# SparkFun_RTK_Express.net
KiCad netlist of a schematic drawn in EAGLE
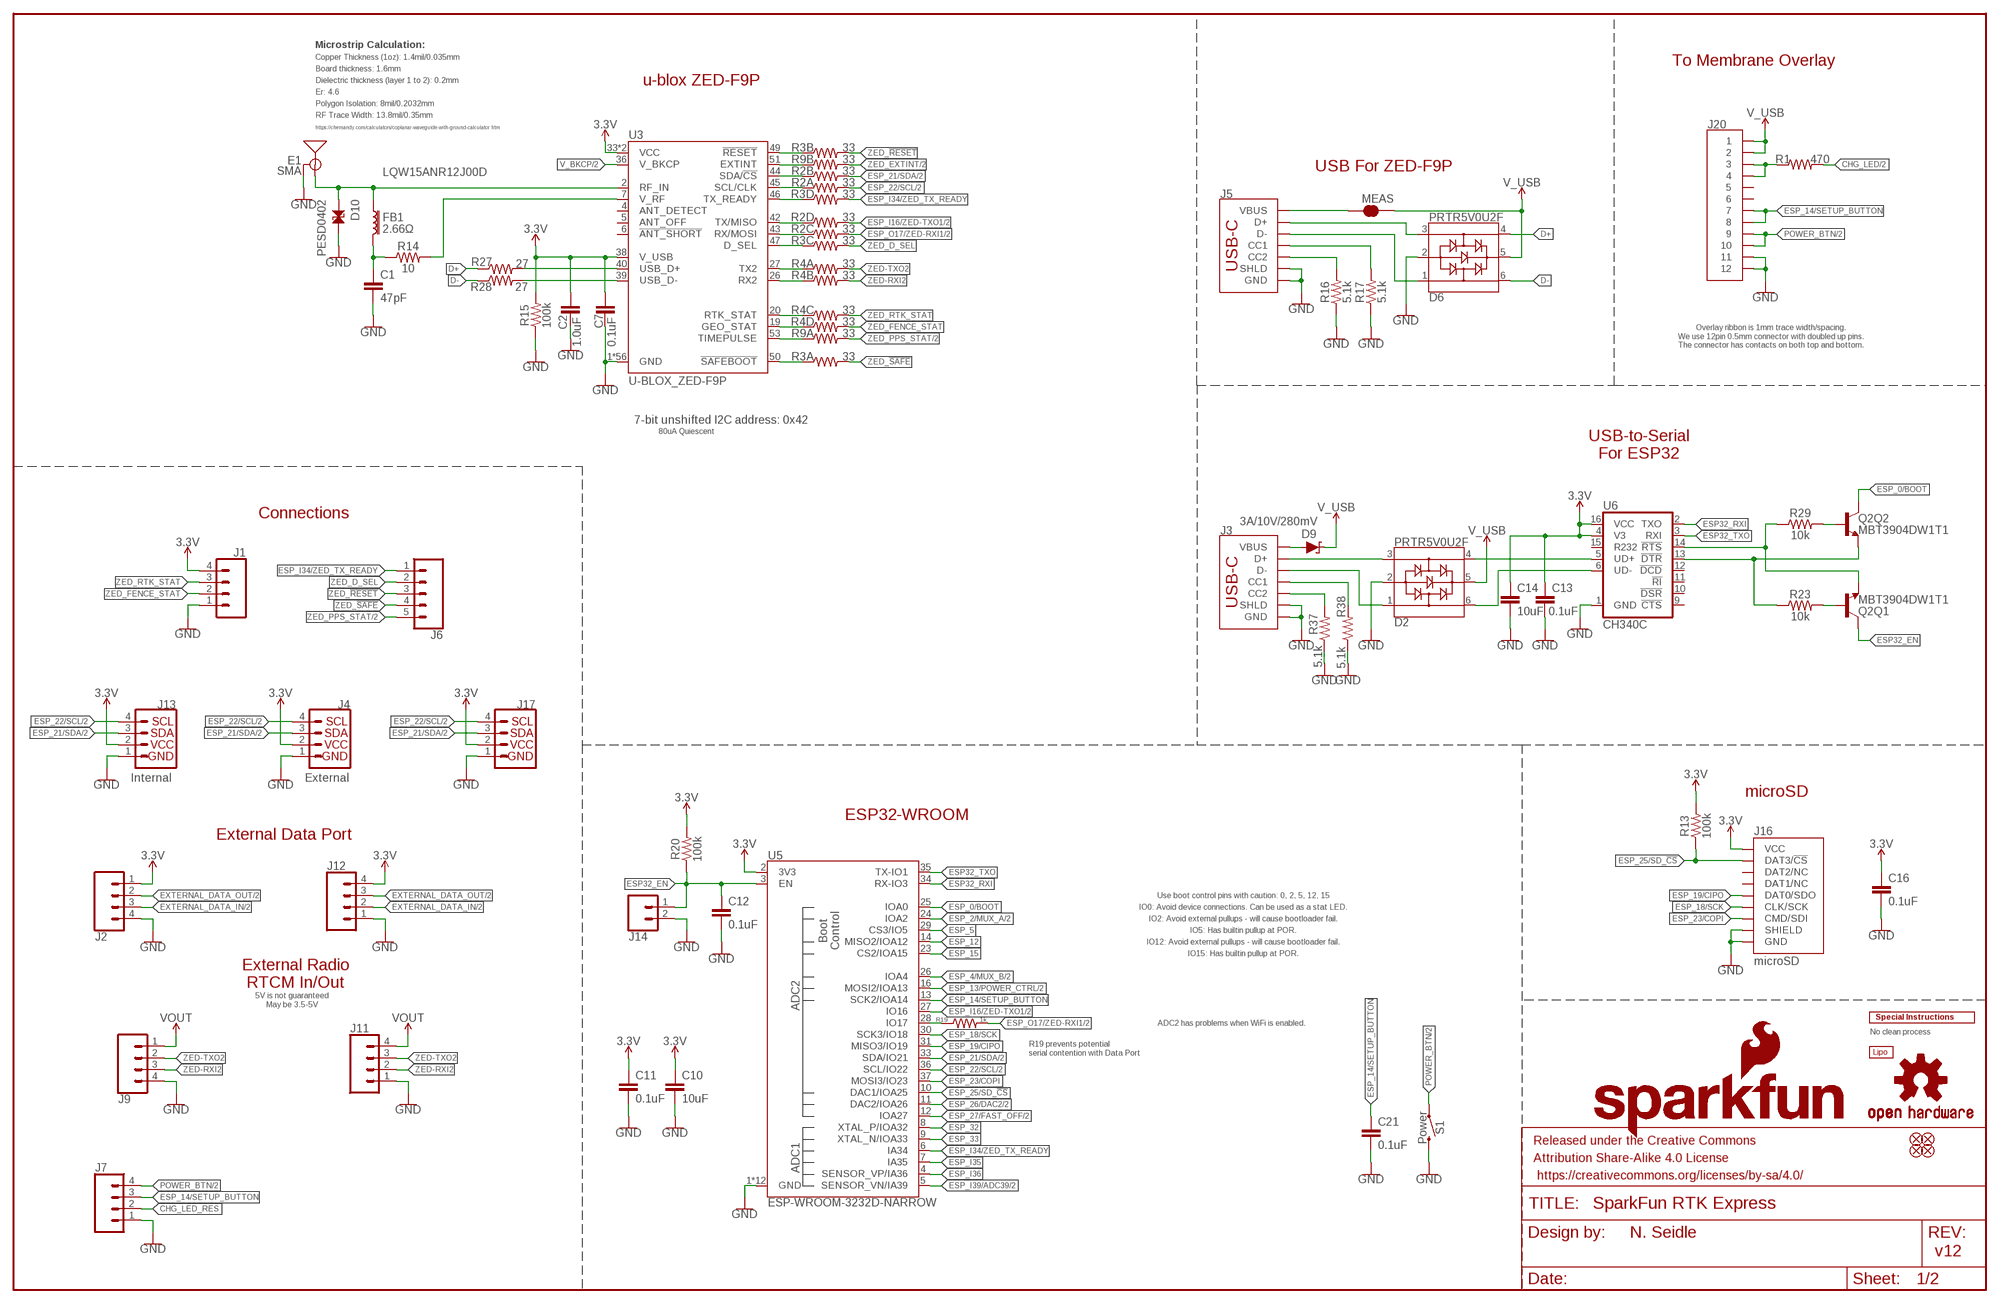
[diagram p0: schematic, sheet 1]
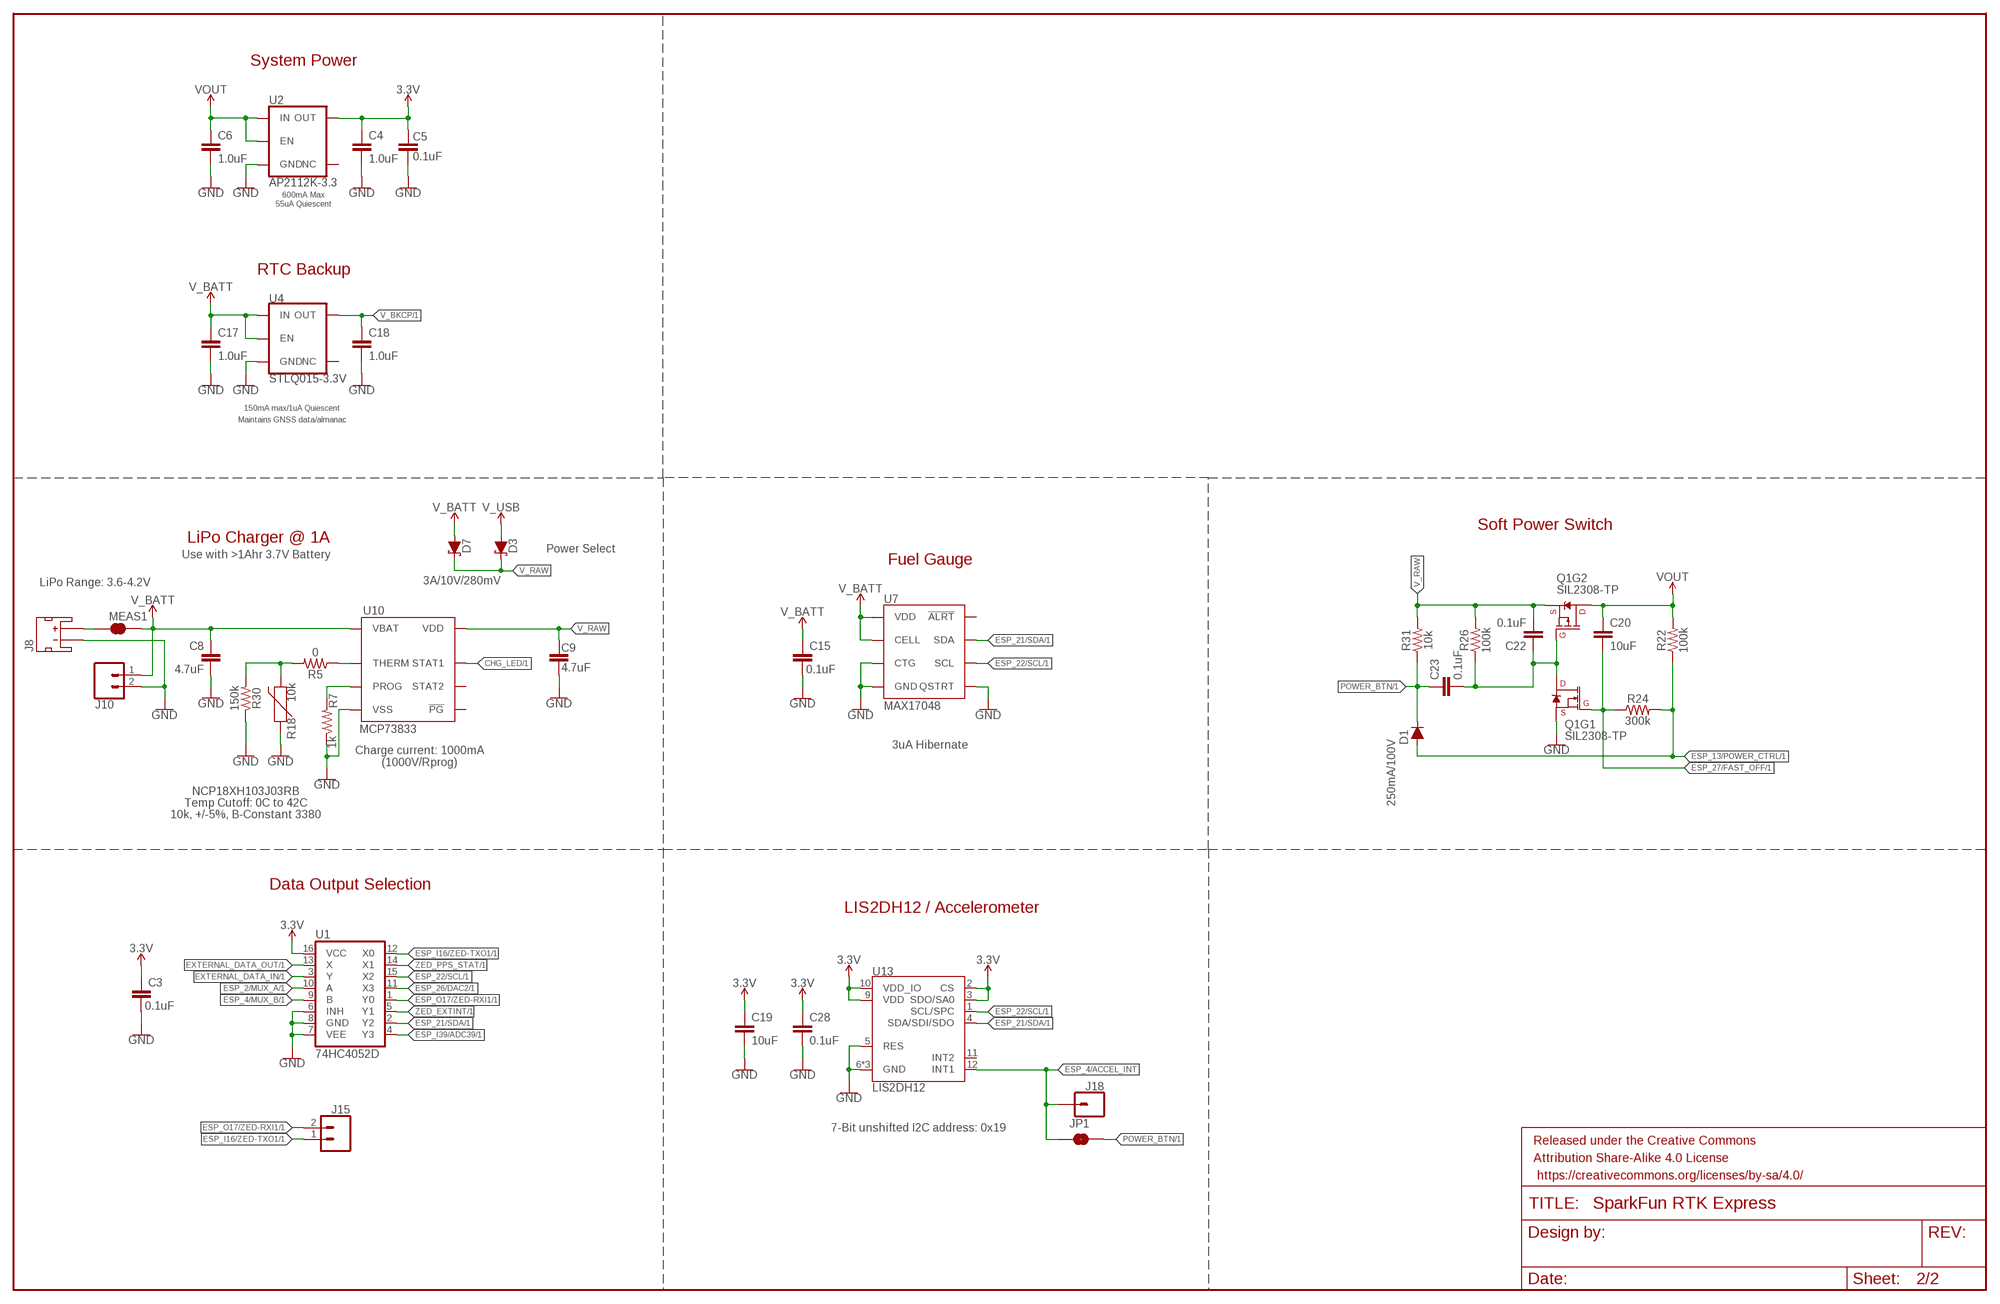
[diagram p1: schematic, sheet 2]

(export (version "E")
  (design (tool "Eeschema 10.0.6"))
  (components
    (comp (ref "C3")
      (value "0.1uF")
      (footprint "eagle-import:0603")
      (libsource (lib "eagle-import") (part "0.1UF-0603-25V-(+80/-20%)"))
    )
    (comp (ref "C4")
      (value "1.0uF")
      (footprint "eagle-import:0603")
      (libsource (lib "eagle-import") (part "1.0UF-0603-16V-10%-X7R"))
    )
    (comp (ref "C5")
      (value "0.1uF")
      (footprint "eagle-import:0603")
      (libsource (lib "eagle-import") (part "0.1UF-0603-25V-5%"))
    )
    (comp (ref "C6")
      (value "1.0uF")
      (footprint "eagle-import:0603")
      (libsource (lib "eagle-import") (part "1.0UF-0603-16V-10%-X7R"))
    )
    (comp (ref "C8")
      (value "4.7uF")
      (footprint "eagle-import:0603")
      (libsource (lib "eagle-import") (part "4.7UF-0603-35V-(20%)"))
    )
    (comp (ref "C9")
      (value "4.7uF")
      (footprint "eagle-import:0603")
      (libsource (lib "eagle-import") (part "4.7UF-0603-35V-(20%)"))
    )
    (comp (ref "C15")
      (value "0.1uF")
      (footprint "eagle-import:0603")
      (libsource (lib "eagle-import") (part "0.1UF-0603-25V-(+80/-20%)"))
    )
    (comp (ref "C17")
      (value "1.0uF")
      (footprint "eagle-import:0603")
      (libsource (lib "eagle-import") (part "1.0UF-0603-16V-10%-X7R"))
    )
    (comp (ref "C18")
      (value "1.0uF")
      (footprint "eagle-import:0603")
      (libsource (lib "eagle-import") (part "1.0UF-0603-16V-10%-X7R"))
    )
    (comp (ref "C19")
      (value "10uF")
      (footprint "eagle-import:0603")
      (libsource (lib "eagle-import") (part "10UF-0603-6.3V-20%"))
    )
    (comp (ref "C20")
      (value "10uF")
      (footprint "eagle-import:0603")
      (libsource (lib "eagle-import") (part "10UF-0603-6.3V-20%"))
    )
    (comp (ref "C22")
      (value "0.1uF")
      (footprint "eagle-import:0603")
      (libsource (lib "eagle-import") (part "0.1UF-0603-25V-5%"))
    )
    (comp (ref "C23")
      (value "0.1uF")
      (footprint "eagle-import:0603")
      (libsource (lib "eagle-import") (part "0.1UF-0603-25V-5%"))
    )
    (comp (ref "C28")
      (value "0.1uF")
      (footprint "eagle-import:0603")
      (libsource (lib "eagle-import") (part "0.1UF-0603-25V-(+80/-20%)"))
    )
    (comp (ref "D1")
      (value "250mA/100V")
      (footprint "eagle-import:SOD-323")
      (libsource (lib "eagle-import") (part "DIODE-BAS16J"))
    )
    (comp (ref "D3")
      (value "3A/10V/280mV")
      (footprint "eagle-import:SOD-323")
      (libsource (lib "eagle-import") (part "DIODE-SCHOTTKY-BAT60A"))
    )
    (comp (ref "D7")
      (value "3A/10V/280mV")
      (footprint "eagle-import:SOD-323")
      (libsource (lib "eagle-import") (part "DIODE-SCHOTTKY-BAT60A"))
    )
    (comp (ref "FRAME3")
      (value "FRAME-LEDGERNO_FOOTPRINT")
      (footprint "eagle-import:DUMMY")
      (libsource (lib "eagle-import") (part "FRAME-LEDGERNO_FOOTPRINT"))
    )
    (comp (ref "J8")
      (value "JST_2MM_MALE")
      (footprint "eagle-import:JST-2-SMD")
      (libsource (lib "eagle-import") (part "JST_2MM_MALE"))
    )
    (comp (ref "J10")
      (value "CONN_021X02_NO_SILK")
      (footprint "eagle-import:1X02_NO_SILK")
      (libsource (lib "eagle-import") (part "CONN_021X02_NO_SILK"))
    )
    (comp (ref "J15")
      (value "CONN_021X02_NO_SILK")
      (footprint "eagle-import:1X02_NO_SILK")
      (libsource (lib "eagle-import") (part "CONN_021X02_NO_SILK"))
    )
    (comp (ref "J18")
      (value "CONN_01PTH_NO_SILK_YES_STOP")
      (footprint "eagle-import:1X01_NO_SILK")
      (libsource (lib "eagle-import") (part "CONN_01PTH_NO_SILK_YES_STOP"))
    )
    (comp (ref "JP1")
      (value "JUMPER-SMT_2_NO_SILK")
      (footprint "eagle-import:SMT-JUMPER_2_NO_SILK")
      (libsource (lib "eagle-import") (part "JUMPER-SMT_2_NO_SILK"))
    )
    (comp (ref "MEAS1")
      (value "JUMPER-COMBO_2_NC_TRACE")
      (footprint "eagle-import:COMBO-JUMPER_2_NC_TRACE")
      (libsource (lib "eagle-import") (part "JUMPER-COMBO_2_NC_TRACE"))
    )
    (comp (ref "Q1")
      (value "SIL2308-TP")
      (footprint "eagle-import:SOT26")
      (libsource (lib "eagle-import") (part "MOSFET_COMPLIMENTARY_PAIR-SIL2308"))
    )
    (comp (ref "R5")
      (value "0")
      (footprint "eagle-import:0603")
      (libsource (lib "eagle-import") (part "0OHM-0603-1/10W"))
    )
    (comp (ref "R7")
      (value "1k")
      (footprint "eagle-import:0603")
      (libsource (lib "eagle-import") (part "1KOHM-0603-1/10W-1%"))
    )
    (comp (ref "R18")
      (value "10k")
      (footprint "eagle-import:0603")
      (libsource (lib "eagle-import") (part "NTC-THERMISTOR-0603"))
    )
    (comp (ref "R22")
      (value "100k")
      (footprint "eagle-import:0603")
      (libsource (lib "eagle-import") (part "100KOHM-0603-1/10W-1%"))
    )
    (comp (ref "R24")
      (value "300k")
      (footprint "eagle-import:0603")
      (libsource (lib "eagle-import") (part "300KOHM-0603-1/10W-1%"))
    )
    (comp (ref "R26")
      (value "100k")
      (footprint "eagle-import:0603")
      (libsource (lib "eagle-import") (part "100KOHM-0603-1/10W-1%"))
    )
    (comp (ref "R30")
      (value "150k")
      (footprint "eagle-import:0603")
      (libsource (lib "eagle-import") (part "150KOHM-0603-1/10W-1%"))
    )
    (comp (ref "R31")
      (value "10k")
      (footprint "eagle-import:0603")
      (libsource (lib "eagle-import") (part "10KOHM-0603-1/10W-1%"))
    )
    (comp (ref "U1")
      (value "74HC4052D")
      (footprint "eagle-import:SO16")
      (libsource (lib "eagle-import") (part "744052DHC"))
    )
    (comp (ref "U2")
      (value "AP2112K-3.3")
      (footprint "eagle-import:SOT23-5")
      (libsource (lib "eagle-import") (part "V_REG_AP2112K-3.3V"))
    )
    (comp (ref "U4")
      (value "STLQ015-3.3V")
      (footprint "eagle-import:SOT23-5")
      (libsource (lib "eagle-import") (part "STLQ015-3.3V"))
    )
    (comp (ref "U7")
      (value "MAX17048")
      (footprint "eagle-import:DFN-8")
      (libsource (lib "eagle-import") (part "MAX17048DFN8"))
    )
    (comp (ref "U10")
      (value "MCP73833")
      (footprint "eagle-import:DFN-10")
      (libsource (lib "eagle-import") (part "MCP73833"))
    )
    (comp (ref "U13")
      (value "LIS2DH12")
      (footprint "eagle-import:LGA-12-LISDH12")
      (libsource (lib "eagle-import") (part "LIS2DH12"))
    )
    (comp (ref "BT1")
      (value "LIPO-OUTLINE1000")
      (footprint "eagle-import:LIPO-1000")
      (libsource (lib "eagle-import") (part "LIPO-OUTLINE1000"))
    )
    (comp (ref "C1")
      (value "47pF")
      (footprint "eagle-import:0402")
      (libsource (lib "eagle-import") (part "47PF-0402-25V-5%-X7R"))
    )
    (comp (ref "C2")
      (value "1.0uF")
      (footprint "eagle-import:0603")
      (libsource (lib "eagle-import") (part "1.0UF-0603-16V-10%-X7R"))
    )
    (comp (ref "C7")
      (value "0.1uF")
      (footprint "eagle-import:0603")
      (libsource (lib "eagle-import") (part "0.1UF-0603-25V-5%"))
    )
    (comp (ref "C10")
      (value "10uF")
      (footprint "eagle-import:0603")
      (libsource (lib "eagle-import") (part "10UF-0603-6.3V-20%"))
    )
    (comp (ref "C11")
      (value "0.1uF")
      (footprint "eagle-import:0603")
      (libsource (lib "eagle-import") (part "0.1UF-0603-25V-(+80/-20%)"))
    )
    (comp (ref "C12")
      (value "0.1uF")
      (footprint "eagle-import:0603")
      (libsource (lib "eagle-import") (part "0.1UF-0603-25V-(+80/-20%)"))
    )
    (comp (ref "C13")
      (value "0.1uF")
      (footprint "eagle-import:0603")
      (libsource (lib "eagle-import") (part "0.1UF-0603-25V-(+80/-20%)"))
    )
    (comp (ref "C14")
      (value "10uF")
      (footprint "eagle-import:0603")
      (libsource (lib "eagle-import") (part "10UF-0603-6.3V-20%"))
    )
    (comp (ref "C16")
      (value "0.1uF")
      (footprint "eagle-import:0603")
      (libsource (lib "eagle-import") (part "0.1UF-0603-25V-(+80/-20%)"))
    )
    (comp (ref "C21")
      (value "0.1uF")
      (footprint "eagle-import:0603")
      (libsource (lib "eagle-import") (part "0.1UF-0603-25V-(+80/-20%)"))
    )
    (comp (ref "D2")
      (value "PRTR5V0U2F")
      (footprint "eagle-import:SOT886")
      (libsource (lib "eagle-import") (part "PRTR5V0U2F"))
    )
    (comp (ref "D6")
      (value "PRTR5V0U2F")
      (footprint "eagle-import:SOT886")
      (libsource (lib "eagle-import") (part "PRTR5V0U2F"))
    )
    (comp (ref "D9")
      (value "3A/10V/280mV")
      (footprint "eagle-import:SOD-323")
      (libsource (lib "eagle-import") (part "DIODE-SCHOTTKY-BAT60A"))
    )
    (comp (ref "D10")
      (value "PESD0402")
      (footprint "eagle-import:0402")
      (fields
        (field (name "DIGIKEY_PART") "PESD0402-140CT-ND")
        (field (name "MOUSE_PART") "650-PESD0402-140")
      )
      (libsource (lib "eagle-import") (part "PESD0402"))
    )
    (comp (ref "E1")
      (value "SMA")
      (footprint "eagle-import:SMA-EDGE")
      (libsource (lib "eagle-import") (part "ANTENNA-SMA-GROUNDEDEDGE_SMA"))
    )
    (comp (ref "FB1")
      (value "2.66Ω")
      (footprint "eagle-import:0402-TIGHT")
      (libsource (lib "eagle-import") (part "FERRITE_BEAD-0402-2.66OHM-1GHZ"))
    )
    (comp (ref "FRAME2")
      (value "FRAME-LEDGER")
      (footprint "eagle-import:CREATIVE_COMMONS")
      (libsource (lib "eagle-import") (part "FRAME-LEDGER"))
    )
    (comp (ref "J1")
      (value "CONN_041X04_NO_SILK_NO_POP")
      (footprint "eagle-import:1X04_NO_SILK")
      (libsource (lib "eagle-import") (part "CONN_041X04_NO_SILK_NO_POP"))
    )
    (comp (ref "J2")
      (value "CONN_04JST-SMD-LOCKING")
      (footprint "eagle-import:JST-4-SMD-1.25MM-LOCKING")
      (libsource (lib "eagle-import") (part "CONN_04JST-SMD-LOCKING"))
    )
    (comp (ref "J3")
      (value "USB Female Type C Connector")
      (footprint "eagle-import:USB-C-16P_4LAYER-PADS")
      (libsource (lib "eagle-import") (part "USB_C_4-LAYER_PADS"))
    )
    (comp (ref "J4")
      (value "External")
      (footprint "eagle-import:JST04_1MM_RA")
      (libsource (lib "eagle-import") (part "I2C_STANDARDQWIIC"))
    )
    (comp (ref "J5")
      (value "USB Female Type C Connector")
      (footprint "eagle-import:USB-C-16P_4LAYER-PADS")
      (libsource (lib "eagle-import") (part "USB_C_4-LAYER_PADS"))
    )
    (comp (ref "J6")
      (value "CONN_05NO_SILK")
      (footprint "eagle-import:1X05_NO_SILK")
      (libsource (lib "eagle-import") (part "CONN_05NO_SILK"))
    )
    (comp (ref "J7")
      (value "CONN_041X04_NO_SILK_NO_POP")
      (footprint "eagle-import:1X04_NO_SILK")
      (libsource (lib "eagle-import") (part "CONN_041X04_NO_SILK_NO_POP"))
    )
    (comp (ref "J9")
      (value "CONN_04JST-SMD-LOCKING")
      (footprint "eagle-import:JST-4-SMD-1.25MM-LOCKING")
      (libsource (lib "eagle-import") (part "CONN_04JST-SMD-LOCKING"))
    )
    (comp (ref "J11")
      (value "CONN_041X04_NO_SILK_NO_POP")
      (footprint "eagle-import:1X04_NO_SILK")
      (libsource (lib "eagle-import") (part "CONN_041X04_NO_SILK_NO_POP"))
    )
    (comp (ref "J12")
      (value "CONN_041X04_NO_SILK_NO_POP")
      (footprint "eagle-import:1X04_NO_SILK")
      (libsource (lib "eagle-import") (part "CONN_041X04_NO_SILK_NO_POP"))
    )
    (comp (ref "J13")
      (value "Internal")
      (footprint "eagle-import:JST04_1MM_RA")
      (libsource (lib "eagle-import") (part "I2C_STANDARDQWIIC"))
    )
    (comp (ref "J14")
      (value "CONN_021X02_NO_SILK")
      (footprint "eagle-import:1X02_NO_SILK")
      (libsource (lib "eagle-import") (part "CONN_021X02_NO_SILK"))
    )
    (comp (ref "J16")
      (value "microSD")
      (footprint "eagle-import:MICRO-SD-SOCKET")
      (libsource (lib "eagle-import") (part "MICRO-SD-SDIOPUSH-PUSH"))
    )
    (comp (ref "J17")
      (value "Qwiic Right Angle")
      (footprint "eagle-import:1X04_NO_SILK")
      (libsource (lib "eagle-import") (part "I2C_STANDARD_NO_SILK"))
    )
    (comp (ref "J20")
      (value "FPC_12_0.5MM_BACKFLIP")
      (footprint "eagle-import:FPC_12_DOUBLESIDED_BACKFLIP")
      (libsource (lib "eagle-import") (part "FPC_12_0.5MM_BACKFLIP"))
    )
    (comp (ref "JP21")
      (value "FIDUCIALUFIDUCIAL")
      (footprint "eagle-import:FIDUCIAL-MICRO")
      (libsource (lib "eagle-import") (part "FIDUCIALUFIDUCIAL"))
    )
    (comp (ref "JP61")
      (value "FIDUCIALUFIDUCIAL")
      (footprint "eagle-import:FIDUCIAL-MICRO")
      (libsource (lib "eagle-import") (part "FIDUCIALUFIDUCIAL"))
    )
    (comp (ref "JP71")
      (value "FIDUCIALUFIDUCIAL")
      (footprint "eagle-import:FIDUCIAL-MICRO")
      (libsource (lib "eagle-import") (part "FIDUCIALUFIDUCIAL"))
    )
    (comp (ref "JP81")
      (value "FIDUCIALUFIDUCIAL")
      (footprint "eagle-import:FIDUCIAL-MICRO")
      (libsource (lib "eagle-import") (part "FIDUCIALUFIDUCIAL"))
    )
    (comp (ref "LOGO1")
      (value "OSHW-LOGOMINI")
      (footprint "eagle-import:OSHW-LOGO-MINI")
      (libsource (lib "eagle-import") (part "OSHW-LOGOMINI"))
    )
    (comp (ref "LOGO2")
      (value "SFE_LOGO_NAME_FLAME.1_INCH")
      (footprint "eagle-import:SFE_LOGO_NAME_FLAME_.1")
      (libsource (lib "eagle-import") (part "SFE_LOGO_NAME_FLAME.1_INCH"))
    )
    (comp (ref "MEAS")
      (value "JUMPER-COMBO_2_NC_TRACE")
      (footprint "eagle-import:COMBO-JUMPER_2_NC_TRACE")
      (libsource (lib "eagle-import") (part "JUMPER-COMBO_2_NC_TRACE"))
    )
    (comp (ref "Q2")
      (value "MBT3904DW1T1")
      (footprint "eagle-import:SC70-6")
      (libsource (lib "eagle-import") (part "TRANS_NPN_DUAL-MBT3904DW1T1"))
    )
    (comp (ref "R1")
      (value "470")
      (footprint "eagle-import:0603")
      (libsource (lib "eagle-import") (part "470OHM-0603-1/10W-1%"))
    )
    (comp (ref "R2")
      (value "33")
      (footprint "eagle-import:1206_RA")
      (libsource (lib "eagle-import") (part "33OHM_RA-1206-1/16W-5%"))
    )
    (comp (ref "R3")
      (value "33")
      (footprint "eagle-import:1206_RA")
      (libsource (lib "eagle-import") (part "33OHM_RA-1206-1/16W-5%"))
    )
    (comp (ref "R4")
      (value "33")
      (footprint "eagle-import:1206_RA")
      (libsource (lib "eagle-import") (part "33OHM_RA-1206-1/16W-5%"))
    )
    (comp (ref "R9")
      (value "33")
      (footprint "eagle-import:1206_RA")
      (libsource (lib "eagle-import") (part "33OHM_RA-1206-1/16W-5%"))
    )
    (comp (ref "R13")
      (value "100k")
      (footprint "eagle-import:0603")
      (libsource (lib "eagle-import") (part "100KOHM-0603-1/10W-1%"))
    )
    (comp (ref "R14")
      (value "10")
      (footprint "eagle-import:0603")
      (libsource (lib "eagle-import") (part "10OHM-0603-1/10W-1%"))
    )
    (comp (ref "R15")
      (value "100k")
      (footprint "eagle-import:0603")
      (libsource (lib "eagle-import") (part "100KOHM-0603-1/10W-1%"))
    )
    (comp (ref "R16")
      (value "5.1k")
      (footprint "eagle-import:0603")
      (libsource (lib "eagle-import") (part "5.1KOHM5.1KOHM-0603-1/10W-1%"))
    )
    (comp (ref "R17")
      (value "5.1k")
      (footprint "eagle-import:0603")
      (libsource (lib "eagle-import") (part "5.1KOHM5.1KOHM-0603-1/10W-1%"))
    )
    (comp (ref "R19")
      (value "1k")
      (footprint "eagle-import:0603")
      (libsource (lib "eagle-import") (part "1KOHM-0603-1/10W-1%"))
    )
    (comp (ref "R20")
      (value "100k")
      (footprint "eagle-import:0603")
      (libsource (lib "eagle-import") (part "100KOHM-0603-1/10W-1%"))
    )
    (comp (ref "R23")
      (value "10k")
      (footprint "eagle-import:0603")
      (libsource (lib "eagle-import") (part "10KOHM-0603-1/10W-1%"))
    )
    (comp (ref "R27")
      (value "27")
      (footprint "eagle-import:0603")
      (libsource (lib "eagle-import") (part "27OHM-0603-1/10W-1%"))
    )
    (comp (ref "R28")
      (value "27")
      (footprint "eagle-import:0603")
      (libsource (lib "eagle-import") (part "27OHM-0603-1/10W-1%"))
    )
    (comp (ref "R29")
      (value "10k")
      (footprint "eagle-import:0603")
      (libsource (lib "eagle-import") (part "10KOHM-0603-1/10W-1%"))
    )
    (comp (ref "R37")
      (value "5.1k")
      (footprint "eagle-import:0603")
      (libsource (lib "eagle-import") (part "5.1KOHM5.1KOHM-0603-1/10W-1%"))
    )
    (comp (ref "R38")
      (value "5.1k")
      (footprint "eagle-import:0603")
      (libsource (lib "eagle-import") (part "5.1KOHM5.1KOHM-0603-1/10W-1%"))
    )
    (comp (ref "S1")
      (value "Power")
      (footprint "eagle-import:TACTILE_SWITCH_SMD_5.2MM")
      (libsource (lib "eagle-import") (part "MOMENTARY-SWITCH-SPST-SMD-5.2MM-TALL"))
    )
    (comp (ref "U$2")
      (value "SPECIAL_INSTRUCTIONS-ORDERING")
      (footprint "eagle-import:ORDERING_INSTRUCTIONS")
      (libsource (lib "eagle-import") (part "SPECIAL_INSTRUCTIONS-ORDERING"))
    )
    (comp (ref "U3")
      (value "U-BLOX_ZED-F9P")
      (footprint "eagle-import:ZED-F9P")
      (libsource (lib "eagle-import") (part "U-BLOX_ZED-F9P"))
    )
    (comp (ref "U5")
      (value "ESP-WROOM-3232D-NARROW")
      (footprint "eagle-import:ESP-WROOM-32D-NARROW")
      (libsource (lib "eagle-import") (part "ESP-WROOM-3232D-NARROW"))
    )
    (comp (ref "U6")
      (value "CH340C")
      (footprint "eagle-import:SO016")
      (libsource (lib "eagle-import") (part "CH340C"))
    )
  )
  (nets
    (net (code "1") (name "3.3V") (class "Default")
      (node (ref "C10") (pin "1") (pinfunction "1_1") (pintype "passive"))
      (node (ref "C11") (pin "1") (pinfunction "1_1") (pintype "passive"))
      (node (ref "C13") (pin "1") (pinfunction "1_1") (pintype "passive"))
      (node (ref "C14") (pin "1") (pinfunction "1_1") (pintype "passive"))
      (node (ref "C16") (pin "1") (pinfunction "1_1") (pintype "passive"))
      (node (ref "C19") (pin "1") (pinfunction "1_1") (pintype "passive"))
      (node (ref "C2") (pin "1") (pinfunction "1_1") (pintype "passive"))
      (node (ref "C28") (pin "1") (pinfunction "1_1") (pintype "passive"))
      (node (ref "C3") (pin "1") (pinfunction "1_1") (pintype "passive"))
      (node (ref "C4") (pin "1") (pinfunction "1_1") (pintype "passive"))
      (node (ref "C5") (pin "2") (pinfunction "2_2") (pintype "passive"))
      (node (ref "C7") (pin "2") (pinfunction "2_2") (pintype "passive"))
      (node (ref "J1") (pin "4") (pinfunction "4_4") (pintype "passive"))
      (node (ref "J12") (pin "4") (pinfunction "4_4") (pintype "passive"))
      (node (ref "J13") (pin "2") (pinfunction "2_2") (pintype "power_in"))
      (node (ref "J16") (pin "VCC") (pinfunction "VCC_VCC") (pintype "bidirectional"))
      (node (ref "J17") (pin "2") (pinfunction "2_2") (pintype "power_in"))
      (node (ref "J2") (pin "1") (pinfunction "1_1") (pintype "passive"))
      (node (ref "J4") (pin "2") (pinfunction "2_2") (pintype "power_in"))
      (node (ref "R13") (pin "2") (pinfunction "2_2") (pintype "passive"))
      (node (ref "R15") (pin "2") (pinfunction "2_2") (pintype "passive"))
      (node (ref "R20") (pin "2") (pinfunction "2_2") (pintype "passive"))
      (node (ref "U1") (pin "16") (pinfunction "VCC_16") (pintype "power_in"))
      (node (ref "U13") (pin "10") (pinfunction "VDD_IO_10") (pintype "bidirectional"))
      (node (ref "U13") (pin "2") (pinfunction "CS_2") (pintype "bidirectional"))
      (node (ref "U13") (pin "3") (pinfunction "SDO/SA0_3") (pintype "bidirectional"))
      (node (ref "U13") (pin "9") (pinfunction "VDD_9") (pintype "bidirectional"))
      (node (ref "U2") (pin "5") (pinfunction "OUT_5") (pintype "passive"))
      (node (ref "U3") (pin "33") (pinfunction "VCC_33") (pintype "bidirectional"))
      (node (ref "U3") (pin "34") (pinfunction "VCC_34") (pintype "bidirectional"))
      (node (ref "U3") (pin "38") (pinfunction "V_USB_38") (pintype "bidirectional"))
      (node (ref "U5") (pin "2") (pinfunction "3V3_2") (pintype "bidirectional"))
      (node (ref "U6") (pin "16") (pinfunction "VCC_16") (pintype "bidirectional"))
      (node (ref "U6") (pin "4") (pinfunction "V3_4") (pintype "bidirectional"))
    )
    (net (code "2") (name "CHG_LED") (class "Default")
      (node (ref "R1") (pin "2") (pinfunction "2_2") (pintype "passive"))
      (node (ref "U10") (pin "3") (pinfunction "STAT1_3") (pintype "bidirectional"))
    )
    (net (code "3") (name "CHG_LED_RES") (class "Default")
      (node (ref "J20") (pin "3") (pinfunction "3_3") (pintype "bidirectional"))
      (node (ref "J20") (pin "4") (pinfunction "4_4") (pintype "bidirectional"))
      (node (ref "J7") (pin "2") (pinfunction "2_2") (pintype "passive"))
      (node (ref "R1") (pin "1") (pinfunction "1_1") (pintype "passive"))
    )
    (net (code "4") (name "D+") (class "Default")
      (node (ref "D6") (pin "4") (pinfunction "4_4") (pintype "bidirectional"))
      (node (ref "R27") (pin "1") (pinfunction "1_1") (pintype "passive"))
    )
    (net (code "5") (name "D-") (class "Default")
      (node (ref "D6") (pin "6") (pinfunction "6_6") (pintype "bidirectional"))
      (node (ref "R28") (pin "1") (pinfunction "1_1") (pintype "passive"))
    )
    (net (code "6") (name "ESP32_EN") (class "Default")
      (node (ref "C12") (pin "1") (pinfunction "1_1") (pintype "passive"))
      (node (ref "J14") (pin "1") (pinfunction "1_1") (pintype "passive"))
      (node (ref "Q2") (pin "3") (pinfunction "C_3") (pintype "passive"))
      (node (ref "R20") (pin "1") (pinfunction "1_1") (pintype "passive"))
      (node (ref "U5") (pin "3") (pinfunction "EN_3") (pintype "bidirectional"))
    )
    (net (code "7") (name "ESP32_RXI") (class "Default")
      (node (ref "U5") (pin "34") (pinfunction "RX-IO3_34") (pintype "bidirectional"))
      (node (ref "U6") (pin "2") (pinfunction "TXO_2") (pintype "bidirectional"))
    )
    (net (code "8") (name "ESP32_TXO") (class "Default")
      (node (ref "U5") (pin "35") (pinfunction "TX-IO1_35") (pintype "bidirectional"))
      (node (ref "U6") (pin "3") (pinfunction "RXI_3") (pintype "bidirectional"))
    )
    (net (code "9") (name "ESP_0{slash}BOOT") (class "Default")
      (node (ref "Q2") (pin "6") (pinfunction "C_6") (pintype "passive"))
      (node (ref "U5") (pin "25") (pinfunction "IOA0_25") (pintype "bidirectional"))
    )
    (net (code "10") (name "ESP_2{slash}MUX_A") (class "Default")
      (node (ref "U1") (pin "10") (pinfunction "A_10") (pintype "input"))
      (node (ref "U5") (pin "24") (pinfunction "IOA2_24") (pintype "bidirectional"))
    )
    (net (code "11") (name "ESP_4{slash}ACCEL_INT") (class "Default")
      (node (ref "J18") (pin "1") (pinfunction "1_1") (pintype "passive"))
      (node (ref "JP1") (pin "1") (pinfunction "1_1") (pintype "passive"))
      (node (ref "U13") (pin "12") (pinfunction "INT1_12") (pintype "bidirectional"))
    )
    (net (code "12") (name "ESP_4{slash}MUX_B") (class "Default")
      (node (ref "U1") (pin "9") (pinfunction "B_9") (pintype "input"))
      (node (ref "U5") (pin "26") (pinfunction "IOA4_26") (pintype "bidirectional"))
    )
    (net (code "13") (name "ESP_5") (class "Default")
      (node (ref "U5") (pin "29") (pinfunction "CS3/IO5_29") (pintype "bidirectional"))
    )
    (net (code "14") (name "ESP_12") (class "Default")
      (node (ref "U5") (pin "14") (pinfunction "MISO2/IOA12_14") (pintype "bidirectional"))
    )
    (net (code "15") (name "ESP_13{slash}POWER_CTRL") (class "Default")
      (node (ref "D1") (pin "A") (pinfunction "A_A") (pintype "passive"))
      (node (ref "R22") (pin "1") (pinfunction "1_1") (pintype "passive"))
      (node (ref "R24") (pin "2") (pinfunction "2_2") (pintype "passive"))
      (node (ref "U5") (pin "16") (pinfunction "MOSI2/IOA13_16") (pintype "bidirectional"))
    )
    (net (code "16") (name "ESP_14{slash}SETUP_BUTTON") (class "Default")
      (node (ref "C21") (pin "1") (pinfunction "1_1") (pintype "passive"))
      (node (ref "J20") (pin "7") (pinfunction "7_7") (pintype "bidirectional"))
      (node (ref "J20") (pin "8") (pinfunction "8_8") (pintype "bidirectional"))
      (node (ref "J7") (pin "3") (pinfunction "3_3") (pintype "passive"))
      (node (ref "U5") (pin "13") (pinfunction "SCK2/IOA14_13") (pintype "bidirectional"))
    )
    (net (code "17") (name "ESP_15") (class "Default")
      (node (ref "U5") (pin "23") (pinfunction "CS2/IOA15_23") (pintype "bidirectional"))
    )
    (net (code "18") (name "ESP_18{slash}SCK") (class "Default")
      (node (ref "J16") (pin "SCLK") (pinfunction "CLK/SCK_SCLK") (pintype "bidirectional"))
      (node (ref "U5") (pin "30") (pinfunction "SCK3/IO18_30") (pintype "bidirectional"))
    )
    (net (code "19") (name "ESP_19{slash}CIPO") (class "Default")
      (node (ref "J16") (pin "DO/DAT0") (pinfunction "DAT0/SDO_DO/DAT0") (pintype "bidirectional"))
      (node (ref "U5") (pin "31") (pinfunction "MISO3/IO19_31") (pintype "bidirectional"))
    )
    (net (code "20") (name "ESP_21{slash}SDA") (class "Default")
      (node (ref "J13") (pin "3") (pinfunction "3_3") (pintype "passive"))
      (node (ref "J17") (pin "3") (pinfunction "3_3") (pintype "passive"))
      (node (ref "J4") (pin "3") (pinfunction "3_3") (pintype "passive"))
      (node (ref "R2") (pin "P7") (pinfunction "2_P7") (pintype "passive"))
      (node (ref "U1") (pin "2") (pinfunction "Y2_2") (pintype "bidirectional"))
      (node (ref "U13") (pin "4") (pinfunction "SDA/SDI/SDO_4") (pintype "bidirectional"))
      (node (ref "U5") (pin "33") (pinfunction "SDA/IO21_33") (pintype "bidirectional"))
      (node (ref "U7") (pin "8") (pinfunction "SDA_8") (pintype "input"))
    )
    (net (code "21") (name "ESP_22{slash}SCL") (class "Default")
      (node (ref "J13") (pin "4") (pinfunction "4_4") (pintype "passive"))
      (node (ref "J17") (pin "4") (pinfunction "4_4") (pintype "passive"))
      (node (ref "J4") (pin "4") (pinfunction "4_4") (pintype "passive"))
      (node (ref "R2") (pin "P8") (pinfunction "2_P8") (pintype "passive"))
      (node (ref "U1") (pin "15") (pinfunction "X2_15") (pintype "bidirectional"))
      (node (ref "U13") (pin "1") (pinfunction "SCL/SPC_1") (pintype "bidirectional"))
      (node (ref "U5") (pin "36") (pinfunction "SCL/IO22_36") (pintype "bidirectional"))
      (node (ref "U7") (pin "7") (pinfunction "SCL_7") (pintype "output"))
    )
    (net (code "22") (name "ESP_23{slash}COPI") (class "Default")
      (node (ref "J16") (pin "DI/CMD") (pinfunction "CMD/SDI_DI/CMD") (pintype "bidirectional"))
      (node (ref "U5") (pin "37") (pinfunction "MOSI3/IO23_37") (pintype "bidirectional"))
    )
    (net (code "23") (name "ESP_25{slash}SD_~{CS}") (class "Default")
      (node (ref "J16") (pin "CS/DAT3") (pinfunction "DAT3/~{CS}_CS/DAT3") (pintype "bidirectional"))
      (node (ref "R13") (pin "1") (pinfunction "1_1") (pintype "passive"))
      (node (ref "U5") (pin "10") (pinfunction "DAC1/IOA25_10") (pintype "bidirectional"))
    )
    (net (code "24") (name "ESP_26{slash}DAC2") (class "Default")
      (node (ref "U1") (pin "11") (pinfunction "X3_11") (pintype "bidirectional"))
      (node (ref "U5") (pin "11") (pinfunction "DAC2/IOA26_11") (pintype "bidirectional"))
    )
    (net (code "25") (name "ESP_27{slash}FAST_OFF") (class "Default")
      (node (ref "C20") (pin "2") (pinfunction "2_2") (pintype "passive"))
      (node (ref "Q1") (pin "G1") (pinfunction "G_G1") (pintype "bidirectional"))
      (node (ref "R24") (pin "1") (pinfunction "1_1") (pintype "passive"))
      (node (ref "U5") (pin "12") (pinfunction "IOA27_12") (pintype "bidirectional"))
    )
    (net (code "26") (name "ESP_32") (class "Default")
      (node (ref "U5") (pin "8") (pinfunction "XTAL_P/IOA32_8") (pintype "bidirectional"))
    )
    (net (code "27") (name "ESP_33") (class "Default")
      (node (ref "U5") (pin "9") (pinfunction "XTAL_N/IOA33_9") (pintype "bidirectional"))
    )
    (net (code "28") (name "ESP_I16{slash}ZED-TXO1") (class "Default")
      (node (ref "J15") (pin "1") (pinfunction "1_1") (pintype "passive"))
      (node (ref "R2") (pin "P5") (pinfunction "2_P5") (pintype "passive"))
      (node (ref "U1") (pin "12") (pinfunction "X0_12") (pintype "bidirectional"))
      (node (ref "U5") (pin "27") (pinfunction "IO16_27") (pintype "bidirectional"))
    )
    (net (code "29") (name "ESP_I34{slash}ZED_TX_READY") (class "Default")
      (node (ref "J6") (pin "1") (pinfunction "1_1") (pintype "passive"))
      (node (ref "R3") (pin "P5") (pinfunction "2_P5") (pintype "passive"))
      (node (ref "U5") (pin "6") (pinfunction "IA34_6") (pintype "bidirectional"))
    )
    (net (code "30") (name "ESP_I35") (class "Default")
      (node (ref "U5") (pin "7") (pinfunction "IA35_7") (pintype "bidirectional"))
    )
    (net (code "31") (name "ESP_I36") (class "Default")
      (node (ref "U5") (pin "4") (pinfunction "SENSOR_VP/IA36_4") (pintype "bidirectional"))
    )
    (net (code "32") (name "ESP_I39{slash}ADC39") (class "Default")
      (node (ref "U1") (pin "4") (pinfunction "Y3_4") (pintype "bidirectional"))
      (node (ref "U5") (pin "5") (pinfunction "SENSOR_VN/IA39_5") (pintype "bidirectional"))
    )
    (net (code "33") (name "ESP_O17{slash}ZED-RXI1") (class "Default")
      (node (ref "J15") (pin "2") (pinfunction "2_2") (pintype "passive"))
      (node (ref "R19") (pin "2") (pinfunction "2_2") (pintype "passive"))
      (node (ref "R2") (pin "P6") (pinfunction "2_P6") (pintype "passive"))
      (node (ref "U1") (pin "1") (pinfunction "Y0_1") (pintype "bidirectional"))
    )
    (net (code "34") (name "EXTERNAL_DATA_IN") (class "Default")
      (node (ref "J12") (pin "2") (pinfunction "2_2") (pintype "passive"))
      (node (ref "J2") (pin "3") (pinfunction "3_3") (pintype "passive"))
      (node (ref "U1") (pin "3") (pinfunction "Y_3") (pintype "bidirectional"))
    )
    (net (code "35") (name "EXTERNAL_DATA_OUT") (class "Default")
      (node (ref "J12") (pin "3") (pinfunction "3_3") (pintype "passive"))
      (node (ref "J2") (pin "2") (pinfunction "2_2") (pintype "passive"))
      (node (ref "U1") (pin "13") (pinfunction "X_13") (pintype "bidirectional"))
    )
    (net (code "36") (name "GND") (class "Default")
      (node (ref "C1") (pin "2") (pinfunction "2_2") (pintype "passive"))
      (node (ref "C10") (pin "2") (pinfunction "2_2") (pintype "passive"))
      (node (ref "C11") (pin "2") (pinfunction "2_2") (pintype "passive"))
      (node (ref "C12") (pin "2") (pinfunction "2_2") (pintype "passive"))
      (node (ref "C13") (pin "2") (pinfunction "2_2") (pintype "passive"))
      (node (ref "C14") (pin "2") (pinfunction "2_2") (pintype "passive"))
      (node (ref "C15") (pin "2") (pinfunction "2_2") (pintype "passive"))
      (node (ref "C16") (pin "2") (pinfunction "2_2") (pintype "passive"))
      (node (ref "C17") (pin "2") (pinfunction "2_2") (pintype "passive"))
      (node (ref "C18") (pin "2") (pinfunction "2_2") (pintype "passive"))
      (node (ref "C19") (pin "2") (pinfunction "2_2") (pintype "passive"))
      (node (ref "C2") (pin "2") (pinfunction "2_2") (pintype "passive"))
      (node (ref "C21") (pin "2") (pinfunction "2_2") (pintype "passive"))
      (node (ref "C28") (pin "2") (pinfunction "2_2") (pintype "passive"))
      (node (ref "C3") (pin "2") (pinfunction "2_2") (pintype "passive"))
      (node (ref "C4") (pin "2") (pinfunction "2_2") (pintype "passive"))
      (node (ref "C5") (pin "1") (pinfunction "1_1") (pintype "passive"))
      (node (ref "C6") (pin "2") (pinfunction "2_2") (pintype "passive"))
      (node (ref "C7") (pin "1") (pinfunction "1_1") (pintype "passive"))
      (node (ref "C8") (pin "2") (pinfunction "2_2") (pintype "passive"))
      (node (ref "C9") (pin "2") (pinfunction "2_2") (pintype "passive"))
      (node (ref "D10") (pin "2") (pinfunction "2_2") (pintype "bidirectional"))
      (node (ref "D2") (pin "2") (pinfunction "2_2") (pintype "power_in"))
      (node (ref "D6") (pin "2") (pinfunction "2_2") (pintype "power_in"))
      (node (ref "E1") (pin "GND@0") (pinfunction "GND_GND@0") (pintype "bidirectional"))
      (node (ref "E1") (pin "GND@1") (pinfunction "GND_GND@1") (pintype "bidirectional"))
      (node (ref "E1") (pin "GND@2") (pinfunction "GND_GND@2") (pintype "bidirectional"))
      (node (ref "E1") (pin "GND@3") (pinfunction "GND_GND@3") (pintype "bidirectional"))
      (node (ref "J1") (pin "1") (pinfunction "1_1") (pintype "passive"))
      (node (ref "J10") (pin "2") (pinfunction "2_2") (pintype "passive"))
      (node (ref "J11") (pin "1") (pinfunction "1_1") (pintype "passive"))
      (node (ref "J12") (pin "1") (pinfunction "1_1") (pintype "passive"))
      (node (ref "J13") (pin "1") (pinfunction "1_1") (pintype "power_in"))
      (node (ref "J14") (pin "2") (pinfunction "2_2") (pintype "passive"))
      (node (ref "J16") (pin "CD1") (pinfunction "SHIELD_CD1") (pintype "bidirectional"))
      (node (ref "J16") (pin "GND") (pinfunction "GND_GND") (pintype "bidirectional"))
      (node (ref "J16") (pin "GND1") (pinfunction "GND_GND1") (pintype "bidirectional"))
      (node (ref "J16") (pin "GND3") (pinfunction "GND_GND3") (pintype "bidirectional"))
      (node (ref "J17") (pin "1") (pinfunction "1_1") (pintype "power_in"))
      (node (ref "J2") (pin "4") (pinfunction "4_4") (pintype "passive"))
      (node (ref "J20") (pin "11") (pinfunction "11_11") (pintype "bidirectional"))
      (node (ref "J20") (pin "12") (pinfunction "12_12") (pintype "bidirectional"))
      (node (ref "J3") (pin "GND") (pinfunction "GND_GND") (pintype "bidirectional"))
      (node (ref "J3") (pin "GND2") (pinfunction "GND_GND2") (pintype "bidirectional"))
      (node (ref "J3") (pin "SHLD1") (pinfunction "SHLD_SHLD1") (pintype "bidirectional"))
      (node (ref "J3") (pin "SHLD2") (pinfunction "SHLD_SHLD2") (pintype "bidirectional"))
      (node (ref "J3") (pin "SHLD3") (pinfunction "SHLD_SHLD3") (pintype "bidirectional"))
      (node (ref "J3") (pin "SHLD4") (pinfunction "SHLD_SHLD4") (pintype "bidirectional"))
      (node (ref "J4") (pin "1") (pinfunction "1_1") (pintype "power_in"))
      (node (ref "J5") (pin "GND") (pinfunction "GND_GND") (pintype "bidirectional"))
      (node (ref "J5") (pin "GND2") (pinfunction "GND_GND2") (pintype "bidirectional"))
      (node (ref "J5") (pin "SHLD1") (pinfunction "SHLD_SHLD1") (pintype "bidirectional"))
      (node (ref "J5") (pin "SHLD2") (pinfunction "SHLD_SHLD2") (pintype "bidirectional"))
      (node (ref "J5") (pin "SHLD3") (pinfunction "SHLD_SHLD3") (pintype "bidirectional"))
      (node (ref "J5") (pin "SHLD4") (pinfunction "SHLD_SHLD4") (pintype "bidirectional"))
      (node (ref "J7") (pin "1") (pinfunction "1_1") (pintype "passive"))
      (node (ref "J8") (pin "1") (pinfunction "-_1") (pintype "bidirectional"))
      (node (ref "J9") (pin "4") (pinfunction "4_4") (pintype "passive"))
      (node (ref "Q1") (pin "S1") (pinfunction "S_S1") (pintype "bidirectional"))
      (node (ref "R15") (pin "1") (pinfunction "1_1") (pintype "passive"))
      (node (ref "R16") (pin "1") (pinfunction "1_1") (pintype "passive"))
      (node (ref "R17") (pin "1") (pinfunction "1_1") (pintype "passive"))
      (node (ref "R18") (pin "1") (pinfunction "1_1") (pintype "bidirectional"))
      (node (ref "R30") (pin "1") (pinfunction "1_1") (pintype "passive"))
      (node (ref "R37") (pin "1") (pinfunction "1_1") (pintype "passive"))
      (node (ref "R38") (pin "1") (pinfunction "1_1") (pintype "passive"))
      (node (ref "R7") (pin "1") (pinfunction "1_1") (pintype "passive"))
      (node (ref "S1") (pin "3") (pinfunction "2_3") (pintype "passive"))
      (node (ref "U1") (pin "6") (pinfunction "INH_6") (pintype "input"))
      (node (ref "U1") (pin "7") (pinfunction "VEE_7") (pintype "power_in"))
      (node (ref "U1") (pin "8") (pinfunction "GND_8") (pintype "power_in"))
      (node (ref "U10") (pin "11") (pinfunction "VSS_11") (pintype "bidirectional"))
      (node (ref "U10") (pin "5") (pinfunction "VSS_5") (pintype "bidirectional"))
      (node (ref "U13") (pin "5") (pinfunction "RES_5") (pintype "bidirectional"))
      (node (ref "U13") (pin "6") (pinfunction "GND_6") (pintype "bidirectional"))
      (node (ref "U13") (pin "7") (pinfunction "GND_7") (pintype "bidirectional"))
      (node (ref "U13") (pin "8") (pinfunction "GND_8") (pintype "bidirectional"))
      (node (ref "U2") (pin "2") (pinfunction "GND_2") (pintype "input"))
      (node (ref "U3") (pin "1") (pinfunction "GND_1") (pintype "bidirectional"))
      (node (ref "U3") (pin "100") (pinfunction "GND_100") (pintype "bidirectional"))
      (node (ref "U3") (pin "101") (pinfunction "GND_101") (pintype "bidirectional"))
      (node (ref "U3") (pin "102") (pinfunction "GND_102") (pintype "bidirectional"))
      (node (ref "U3") (pin "12") (pinfunction "GND_12") (pintype "bidirectional"))
      (node (ref "U3") (pin "14") (pinfunction "GND_14") (pintype "bidirectional"))
      (node (ref "U3") (pin "3") (pinfunction "GND_3") (pintype "bidirectional"))
      (node (ref "U3") (pin "32") (pinfunction "GND_32") (pintype "bidirectional"))
      (node (ref "U3") (pin "37") (pinfunction "GND_37") (pintype "bidirectional"))
      (node (ref "U3") (pin "41") (pinfunction "GND_41") (pintype "bidirectional"))
      (node (ref "U3") (pin "48") (pinfunction "GND_48") (pintype "bidirectional"))
      (node (ref "U3") (pin "55") (pinfunction "GND_55") (pintype "bidirectional"))
      (node (ref "U3") (pin "56") (pinfunction "GND_56") (pintype "bidirectional"))
      (node (ref "U3") (pin "57") (pinfunction "GND_57") (pintype "bidirectional"))
      (node (ref "U3") (pin "58") (pinfunction "GND_58") (pintype "bidirectional"))
      (node (ref "U3") (pin "59") (pinfunction "GND_59") (pintype "bidirectional"))
      (node (ref "U3") (pin "60") (pinfunction "GND_60") (pintype "bidirectional"))
      (node (ref "U3") (pin "61") (pinfunction "GND_61") (pintype "bidirectional"))
      (node (ref "U3") (pin "62") (pinfunction "GND_62") (pintype "bidirectional"))
      (node (ref "U3") (pin "63") (pinfunction "GND_63") (pintype "bidirectional"))
      (node (ref "U3") (pin "64") (pinfunction "GND_64") (pintype "bidirectional"))
      (node (ref "U3") (pin "65") (pinfunction "GND_65") (pintype "bidirectional"))
      (node (ref "U3") (pin "66") (pinfunction "GND_66") (pintype "bidirectional"))
      (node (ref "U3") (pin "67") (pinfunction "GND_67") (pintype "bidirectional"))
      (node (ref "U3") (pin "68") (pinfunction "GND_68") (pintype "bidirectional"))
      (node (ref "U3") (pin "69") (pinfunction "GND_69") (pintype "bidirectional"))
      (node (ref "U3") (pin "70") (pinfunction "GND_70") (pintype "bidirectional"))
      (node (ref "U3") (pin "71") (pinfunction "GND_71") (pintype "bidirectional"))
      (node (ref "U3") (pin "72") (pinfunction "GND_72") (pintype "bidirectional"))
      (node (ref "U3") (pin "73") (pinfunction "GND_73") (pintype "bidirectional"))
      (node (ref "U3") (pin "74") (pinfunction "GND_74") (pintype "bidirectional"))
      (node (ref "U3") (pin "75") (pinfunction "GND_75") (pintype "bidirectional"))
      (node (ref "U3") (pin "76") (pinfunction "GND_76") (pintype "bidirectional"))
      (node (ref "U3") (pin "77") (pinfunction "GND_77") (pintype "bidirectional"))
      (node (ref "U3") (pin "78") (pinfunction "GND_78") (pintype "bidirectional"))
      (node (ref "U3") (pin "79") (pinfunction "GND_79") (pintype "bidirectional"))
      (node (ref "U3") (pin "80") (pinfunction "GND_80") (pintype "bidirectional"))
      (node (ref "U3") (pin "81") (pinfunction "GND_81") (pintype "bidirectional"))
      (node (ref "U3") (pin "82") (pinfunction "GND_82") (pintype "bidirectional"))
      (node (ref "U3") (pin "83") (pinfunction "GND_83") (pintype "bidirectional"))
      (node (ref "U3") (pin "84") (pinfunction "GND_84") (pintype "bidirectional"))
      (node (ref "U3") (pin "85") (pinfunction "GND_85") (pintype "bidirectional"))
      (node (ref "U3") (pin "86") (pinfunction "GND_86") (pintype "bidirectional"))
      (node (ref "U3") (pin "87") (pinfunction "GND_87") (pintype "bidirectional"))
      (node (ref "U3") (pin "88") (pinfunction "GND_88") (pintype "bidirectional"))
      (node (ref "U3") (pin "89") (pinfunction "GND_89") (pintype "bidirectional"))
      (node (ref "U3") (pin "90") (pinfunction "GND_90") (pintype "bidirectional"))
      (node (ref "U3") (pin "91") (pinfunction "GND_91") (pintype "bidirectional"))
      (node (ref "U3") (pin "92") (pinfunction "GND_92") (pintype "bidirectional"))
      (node (ref "U3") (pin "93") (pinfunction "GND_93") (pintype "bidirectional"))
      (node (ref "U3") (pin "94") (pinfunction "GND_94") (pintype "bidirectional"))
      (node (ref "U3") (pin "95") (pinfunction "GND_95") (pintype "bidirectional"))
      (node (ref "U3") (pin "96") (pinfunction "GND_96") (pintype "bidirectional"))
      (node (ref "U3") (pin "97") (pinfunction "GND_97") (pintype "bidirectional"))
      (node (ref "U3") (pin "98") (pinfunction "GND_98") (pintype "bidirectional"))
      (node (ref "U3") (pin "99") (pinfunction "GND_99") (pintype "bidirectional"))
      (node (ref "U4") (pin "2") (pinfunction "GND_2") (pintype "input"))
      (node (ref "U5") (pin "1") (pinfunction "GND_1") (pintype "bidirectional"))
      (node (ref "U5") (pin "15") (pinfunction "GND_15") (pintype "bidirectional"))
      (node (ref "U5") (pin "38") (pinfunction "GND_38") (pintype "bidirectional"))
      (node (ref "U5") (pin "GND1") (pinfunction "GND_GND1") (pintype "bidirectional"))
      (node (ref "U5") (pin "GNDT1") (pinfunction "GND_GNDT1") (pintype "bidirectional"))
      (node (ref "U5") (pin "GNDT2") (pinfunction "GND_GNDT2") (pintype "bidirectional"))
      (node (ref "U5") (pin "GNDT3") (pinfunction "GND_GNDT3") (pintype "bidirectional"))
      (node (ref "U5") (pin "GNDT4") (pinfunction "GND_GNDT4") (pintype "bidirectional"))
      (node (ref "U5") (pin "GNDT5") (pinfunction "GND_GNDT5") (pintype "bidirectional"))
      (node (ref "U5") (pin "GNDT6") (pinfunction "GND_GNDT6") (pintype "bidirectional"))
      (node (ref "U5") (pin "GNDT7") (pinfunction "GND_GNDT7") (pintype "bidirectional"))
      (node (ref "U5") (pin "GNDT8") (pinfunction "GND_GNDT8") (pintype "bidirectional"))
      (node (ref "U6") (pin "1") (pinfunction "GND_1") (pintype "bidirectional"))
      (node (ref "U7") (pin "1") (pinfunction "CTG_1") (pintype "input"))
      (node (ref "U7") (pin "4") (pinfunction "GND_4") (pintype "bidirectional"))
      (node (ref "U7") (pin "6") (pinfunction "QSTRT_6") (pintype "bidirectional"))
      (node (ref "U7") (pin "9") (pinfunction "GND_9") (pintype "bidirectional"))
    )
    (net (code "37") (name "Net-(C1-Pad1)") (class "Default")
      (node (ref "C1") (pin "1") (pinfunction "1_1") (pintype "passive"))
      (node (ref "FB1") (pin "2") (pinfunction "2_2") (pintype "passive"))
      (node (ref "R14") (pin "1") (pinfunction "1_1") (pintype "passive"))
    )
    (net (code "38") (name "Net-(D2-Pad1)") (class "Default")
      (node (ref "D2") (pin "1") (pinfunction "1_1") (pintype "bidirectional"))
      (node (ref "J3") (pin "A7") (pinfunction "D-_A7") (pintype "bidirectional"))
      (node (ref "J3") (pin "B7") (pinfunction "D-_B7") (pintype "bidirectional"))
    )
    (net (code "39") (name "Net-(D2-Pad3)") (class "Default")
      (node (ref "D2") (pin "3") (pinfunction "3_3") (pintype "bidirectional"))
      (node (ref "J3") (pin "A6") (pinfunction "D+_A6") (pintype "bidirectional"))
      (node (ref "J3") (pin "B6") (pinfunction "D+_B6") (pintype "bidirectional"))
    )
    (net (code "40") (name "Net-(D6-Pad1)") (class "Default")
      (node (ref "D6") (pin "1") (pinfunction "1_1") (pintype "bidirectional"))
      (node (ref "J5") (pin "A7") (pinfunction "D-_A7") (pintype "bidirectional"))
      (node (ref "J5") (pin "B7") (pinfunction "D-_B7") (pintype "bidirectional"))
    )
    (net (code "41") (name "Net-(D6-Pad3)") (class "Default")
      (node (ref "D6") (pin "3") (pinfunction "3_3") (pintype "bidirectional"))
      (node (ref "J5") (pin "A6") (pinfunction "D+_A6") (pintype "bidirectional"))
      (node (ref "J5") (pin "B6") (pinfunction "D+_B6") (pintype "bidirectional"))
    )
    (net (code "42") (name "Net-(D9-PadA)") (class "Default")
      (node (ref "D9") (pin "A") (pinfunction "A_A") (pintype "passive"))
      (node (ref "J3") (pin "VBUS1") (pinfunction "VBUS_VBUS1") (pintype "bidirectional"))
      (node (ref "J3") (pin "VBUS2") (pinfunction "VBUS_VBUS2") (pintype "bidirectional"))
    )
    (net (code "43") (name "Net-(E1-SIGNAL)") (class "Default")
      (node (ref "D10") (pin "1") (pinfunction "1_1") (pintype "bidirectional"))
      (node (ref "E1") (pin "SIG") (pinfunction "SIGNAL_SIG") (pintype "bidirectional"))
      (node (ref "FB1") (pin "1") (pinfunction "1_1") (pintype "passive"))
      (node (ref "U3") (pin "2") (pinfunction "RF_IN_2") (pintype "bidirectional"))
    )
    (net (code "44") (name "Net-(J3-CC1)") (class "Default")
      (node (ref "J3") (pin "A5") (pinfunction "CC1_A5") (pintype "bidirectional"))
      (node (ref "R38") (pin "2") (pinfunction "2_2") (pintype "passive"))
    )
    (net (code "45") (name "Net-(J3-CC2)") (class "Default")
      (node (ref "J3") (pin "B5") (pinfunction "CC2_B5") (pintype "bidirectional"))
      (node (ref "R37") (pin "2") (pinfunction "2_2") (pintype "passive"))
    )
    (net (code "46") (name "Net-(J5-CC1)") (class "Default")
      (node (ref "J5") (pin "A5") (pinfunction "CC1_A5") (pintype "bidirectional"))
      (node (ref "R17") (pin "2") (pinfunction "2_2") (pintype "passive"))
    )
    (net (code "47") (name "Net-(J5-CC2)") (class "Default")
      (node (ref "J5") (pin "B5") (pinfunction "CC2_B5") (pintype "bidirectional"))
      (node (ref "R16") (pin "2") (pinfunction "2_2") (pintype "passive"))
    )
    (net (code "48") (name "Net-(J5-VBUS-PadVBUS1)") (class "Default")
      (node (ref "J5") (pin "VBUS1") (pinfunction "VBUS_VBUS1") (pintype "bidirectional"))
      (node (ref "J5") (pin "VBUS2") (pinfunction "VBUS_VBUS2") (pintype "bidirectional"))
      (node (ref "MEAS") (pin "1") (pinfunction "1_1") (pintype "passive"))
      (node (ref "MEAS") (pin "3") (pinfunction "1_3") (pintype "passive"))
    )
    (net (code "49") (name "Net-(J8-+)") (class "Default")
      (node (ref "J8") (pin "2") (pinfunction "+_2") (pintype "bidirectional"))
      (node (ref "MEAS1") (pin "1") (pinfunction "1_1") (pintype "passive"))
      (node (ref "MEAS1") (pin "3") (pinfunction "1_3") (pintype "passive"))
    )
    (net (code "50") (name "Net-(Q1A-D)") (class "Default")
      (node (ref "C22") (pin "1") (pinfunction "1_1") (pintype "passive"))
      (node (ref "C23") (pin "2") (pinfunction "2_2") (pintype "passive"))
      (node (ref "Q1") (pin "D1") (pinfunction "D_D1") (pintype "bidirectional"))
      (node (ref "Q1") (pin "G2") (pinfunction "G_G2") (pintype "bidirectional"))
      (node (ref "R26") (pin "1") (pinfunction "1_1") (pintype "passive"))
    )
    (net (code "51") (name "Net-(Q2A-B)") (class "Default")
      (node (ref "Q2") (pin "5") (pinfunction "B_5") (pintype "passive"))
      (node (ref "R23") (pin "2") (pinfunction "2_2") (pintype "passive"))
    )
    (net (code "52") (name "Net-(Q2A-E)") (class "Default")
      (node (ref "Q2") (pin "4") (pinfunction "E_4") (pintype "passive"))
      (node (ref "R29") (pin "1") (pinfunction "1_1") (pintype "passive"))
      (node (ref "U6") (pin "14") (pinfunction "~{RTS}_14") (pintype "bidirectional"))
    )
    (net (code "53") (name "Net-(Q2B-B)") (class "Default")
      (node (ref "Q2") (pin "2") (pinfunction "B_2") (pintype "passive"))
      (node (ref "R29") (pin "2") (pinfunction "2_2") (pintype "passive"))
    )
    (net (code "54") (name "Net-(Q2B-E)") (class "Default")
      (node (ref "Q2") (pin "1") (pinfunction "E_1") (pintype "passive"))
      (node (ref "R23") (pin "1") (pinfunction "1_1") (pintype "passive"))
      (node (ref "U6") (pin "13") (pinfunction "~{DTR}_13") (pintype "bidirectional"))
    )
    (net (code "55") (name "Net-(R2A-1)") (class "Default")
      (node (ref "R2") (pin "P1") (pinfunction "1_P1") (pintype "passive"))
      (node (ref "U3") (pin "45") (pinfunction "SCL/CLK_45") (pintype "bidirectional"))
    )
    (net (code "56") (name "Net-(R2B-1)") (class "Default")
      (node (ref "R2") (pin "P2") (pinfunction "1_P2") (pintype "passive"))
      (node (ref "U3") (pin "44") (pinfunction "SDA/~{CS}_44") (pintype "bidirectional"))
    )
    (net (code "57") (name "Net-(R2C-1)") (class "Default")
      (node (ref "R2") (pin "P3") (pinfunction "1_P3") (pintype "passive"))
      (node (ref "U3") (pin "43") (pinfunction "RX/MOSI_43") (pintype "bidirectional"))
    )
    (net (code "58") (name "Net-(R2D-1)") (class "Default")
      (node (ref "R2") (pin "P4") (pinfunction "1_P4") (pintype "passive"))
      (node (ref "U3") (pin "42") (pinfunction "TX/MISO_42") (pintype "bidirectional"))
    )
    (net (code "59") (name "Net-(R3A-1)") (class "Default")
      (node (ref "R3") (pin "P1") (pinfunction "1_P1") (pintype "passive"))
      (node (ref "U3") (pin "50") (pinfunction "~{SAFEBOOT}_50") (pintype "bidirectional"))
    )
    (net (code "60") (name "Net-(R3B-1)") (class "Default")
      (node (ref "R3") (pin "P2") (pinfunction "1_P2") (pintype "passive"))
      (node (ref "U3") (pin "49") (pinfunction "~{RESET}_49") (pintype "bidirectional"))
    )
    (net (code "61") (name "Net-(R3C-1)") (class "Default")
      (node (ref "R3") (pin "P3") (pinfunction "1_P3") (pintype "passive"))
      (node (ref "U3") (pin "47") (pinfunction "D_SEL_47") (pintype "bidirectional"))
    )
    (net (code "62") (name "Net-(R3D-1)") (class "Default")
      (node (ref "R3") (pin "P4") (pinfunction "1_P4") (pintype "passive"))
      (node (ref "U3") (pin "46") (pinfunction "TX_READY_46") (pintype "bidirectional"))
    )
    (net (code "63") (name "Net-(R4A-1)") (class "Default")
      (node (ref "R4") (pin "P1") (pinfunction "1_P1") (pintype "passive"))
      (node (ref "U3") (pin "27") (pinfunction "TX2_27") (pintype "bidirectional"))
    )
    (net (code "64") (name "Net-(R4B-1)") (class "Default")
      (node (ref "R4") (pin "P2") (pinfunction "1_P2") (pintype "passive"))
      (node (ref "U3") (pin "26") (pinfunction "RX2_26") (pintype "bidirectional"))
    )
    (net (code "65") (name "Net-(R4C-1)") (class "Default")
      (node (ref "R4") (pin "P3") (pinfunction "1_P3") (pintype "passive"))
      (node (ref "U3") (pin "20") (pinfunction "RTK_STAT_20") (pintype "bidirectional"))
    )
    (net (code "66") (name "Net-(R4D-1)") (class "Default")
      (node (ref "R4") (pin "P4") (pinfunction "1_P4") (pintype "passive"))
      (node (ref "U3") (pin "19") (pinfunction "GEO_STAT_19") (pintype "bidirectional"))
    )
    (net (code "67") (name "Net-(R9A-1)") (class "Default")
      (node (ref "R9") (pin "P1") (pinfunction "1_P1") (pintype "passive"))
      (node (ref "U3") (pin "53") (pinfunction "TIMEPULSE_53") (pintype "bidirectional"))
    )
    (net (code "68") (name "Net-(R9B-1)") (class "Default")
      (node (ref "R9") (pin "P2") (pinfunction "1_P2") (pintype "passive"))
      (node (ref "U3") (pin "51") (pinfunction "EXTINT_51") (pintype "bidirectional"))
    )
    (net (code "69") (name "Net-(R18-Pad2)") (class "Default")
      (node (ref "R18") (pin "2") (pinfunction "2_2") (pintype "bidirectional"))
      (node (ref "R30") (pin "2") (pinfunction "2_2") (pintype "passive"))
      (node (ref "R5") (pin "2") (pinfunction "2_2") (pintype "passive"))
    )
    (net (code "70") (name "Net-(U3-USB_D+)") (class "Default")
      (node (ref "R27") (pin "2") (pinfunction "2_2") (pintype "passive"))
      (node (ref "U3") (pin "40") (pinfunction "USB_D+_40") (pintype "bidirectional"))
    )
    (net (code "71") (name "Net-(U3-USB_D-)") (class "Default")
      (node (ref "R28") (pin "2") (pinfunction "2_2") (pintype "passive"))
      (node (ref "U3") (pin "39") (pinfunction "USB_D-_39") (pintype "bidirectional"))
    )
    (net (code "72") (name "Net-(U3-V_RF)") (class "Default")
      (node (ref "R14") (pin "2") (pinfunction "2_2") (pintype "passive"))
      (node (ref "U3") (pin "7") (pinfunction "V_RF_7") (pintype "bidirectional"))
    )
    (net (code "73") (name "Net-(U5-IO17)") (class "Default")
      (node (ref "R19") (pin "1") (pinfunction "1_1") (pintype "passive"))
      (node (ref "U5") (pin "28") (pinfunction "IO17_28") (pintype "bidirectional"))
    )
    (net (code "74") (name "Net-(U6-UD+)") (class "Default")
      (node (ref "D2") (pin "4") (pinfunction "4_4") (pintype "bidirectional"))
      (node (ref "U6") (pin "5") (pinfunction "UD+_5") (pintype "bidirectional"))
    )
    (net (code "75") (name "Net-(U6-UD-)") (class "Default")
      (node (ref "D2") (pin "6") (pinfunction "6_6") (pintype "bidirectional"))
      (node (ref "U6") (pin "6") (pinfunction "UD-_6") (pintype "bidirectional"))
    )
    (net (code "76") (name "Net-(U10-PROG)") (class "Default")
      (node (ref "R7") (pin "2") (pinfunction "2_2") (pintype "passive"))
      (node (ref "U10") (pin "6") (pinfunction "PROG_6") (pintype "bidirectional"))
    )
    (net (code "77") (name "Net-(U10-THERM)") (class "Default")
      (node (ref "R5") (pin "1") (pinfunction "1_1") (pintype "passive"))
      (node (ref "U10") (pin "8") (pinfunction "THERM_8") (pintype "bidirectional"))
    )
    (net (code "78") (name "POWER_BTN") (class "Default")
      (node (ref "C23") (pin "1") (pinfunction "1_1") (pintype "passive"))
      (node (ref "D1") (pin "C") (pinfunction "C_C") (pintype "passive"))
      (node (ref "J20") (pin "10") (pinfunction "10_10") (pintype "bidirectional"))
      (node (ref "J20") (pin "9") (pinfunction "9_9") (pintype "bidirectional"))
      (node (ref "J7") (pin "4") (pinfunction "4_4") (pintype "passive"))
      (node (ref "JP1") (pin "2") (pinfunction "2_2") (pintype "passive"))
      (node (ref "R31") (pin "1") (pinfunction "1_1") (pintype "passive"))
      (node (ref "S1") (pin "1") (pinfunction "1_1") (pintype "passive"))
    )
    (net (code "79") (name "VOUT") (class "Default")
      (node (ref "C20") (pin "1") (pinfunction "1_1") (pintype "passive"))
      (node (ref "C6") (pin "1") (pinfunction "1_1") (pintype "passive"))
      (node (ref "J11") (pin "4") (pinfunction "4_4") (pintype "passive"))
      (node (ref "J9") (pin "1") (pinfunction "1_1") (pintype "passive"))
      (node (ref "Q1") (pin "D2") (pinfunction "D_D2") (pintype "bidirectional"))
      (node (ref "R22") (pin "2") (pinfunction "2_2") (pintype "passive"))
      (node (ref "U2") (pin "1") (pinfunction "IN_1") (pintype "input"))
      (node (ref "U2") (pin "3") (pinfunction "EN_3") (pintype "input"))
    )
    (net (code "80") (name "V_BATT") (class "Default")
      (node (ref "C15") (pin "1") (pinfunction "1_1") (pintype "passive"))
      (node (ref "C17") (pin "1") (pinfunction "1_1") (pintype "passive"))
      (node (ref "C8") (pin "1") (pinfunction "1_1") (pintype "passive"))
      (node (ref "D7") (pin "A") (pinfunction "A_A") (pintype "passive"))
      (node (ref "J10") (pin "1") (pinfunction "1_1") (pintype "passive"))
      (node (ref "MEAS1") (pin "2") (pinfunction "2_2") (pintype "passive"))
      (node (ref "MEAS1") (pin "4") (pinfunction "2_4") (pintype "passive"))
      (node (ref "U10") (pin "10") (pinfunction "VBAT_10") (pintype "bidirectional"))
      (node (ref "U10") (pin "9") (pinfunction "VBAT_9") (pintype "bidirectional"))
      (node (ref "U4") (pin "1") (pinfunction "IN_1") (pintype "input"))
      (node (ref "U4") (pin "3") (pinfunction "EN_3") (pintype "input"))
      (node (ref "U7") (pin "2") (pinfunction "CELL_2") (pintype "input"))
      (node (ref "U7") (pin "3") (pinfunction "VDD_3") (pintype "bidirectional"))
    )
    (net (code "81") (name "V_BKCP") (class "Default")
      (node (ref "C18") (pin "1") (pinfunction "1_1") (pintype "passive"))
      (node (ref "U3") (pin "36") (pinfunction "V_BKCP_36") (pintype "bidirectional"))
      (node (ref "U4") (pin "5") (pinfunction "OUT_5") (pintype "passive"))
    )
    (net (code "82") (name "V_RAW") (class "Default")
      (node (ref "C22") (pin "2") (pinfunction "2_2") (pintype "passive"))
      (node (ref "C9") (pin "1") (pinfunction "1_1") (pintype "passive"))
      (node (ref "D3") (pin "C") (pinfunction "C_C") (pintype "passive"))
      (node (ref "D7") (pin "C") (pinfunction "C_C") (pintype "passive"))
      (node (ref "Q1") (pin "S2") (pinfunction "S_S2") (pintype "bidirectional"))
      (node (ref "R26") (pin "2") (pinfunction "2_2") (pintype "passive"))
      (node (ref "R31") (pin "2") (pinfunction "2_2") (pintype "passive"))
      (node (ref "U10") (pin "1") (pinfunction "VDD_1") (pintype "bidirectional"))
      (node (ref "U10") (pin "2") (pinfunction "VDD_2") (pintype "bidirectional"))
    )
    (net (code "83") (name "V_USB") (class "Default")
      (node (ref "D2") (pin "5") (pinfunction "5_5") (pintype "power_in"))
      (node (ref "D3") (pin "A") (pinfunction "A_A") (pintype "passive"))
      (node (ref "D6") (pin "5") (pinfunction "5_5") (pintype "power_in"))
      (node (ref "D9") (pin "C") (pinfunction "C_C") (pintype "passive"))
      (node (ref "J20") (pin "1") (pinfunction "1_1") (pintype "bidirectional"))
      (node (ref "J20") (pin "2") (pinfunction "2_2") (pintype "bidirectional"))
      (node (ref "MEAS") (pin "2") (pinfunction "2_2") (pintype "passive"))
      (node (ref "MEAS") (pin "4") (pinfunction "2_4") (pintype "passive"))
    )
    (net (code "84") (name "ZED-RXI2") (class "Default")
      (node (ref "J11") (pin "2") (pinfunction "2_2") (pintype "passive"))
      (node (ref "J9") (pin "3") (pinfunction "3_3") (pintype "passive"))
      (node (ref "R4") (pin "P7") (pinfunction "2_P7") (pintype "passive"))
    )
    (net (code "85") (name "ZED-TXO2") (class "Default")
      (node (ref "J11") (pin "3") (pinfunction "3_3") (pintype "passive"))
      (node (ref "J9") (pin "2") (pinfunction "2_2") (pintype "passive"))
      (node (ref "R4") (pin "P8") (pinfunction "2_P8") (pintype "passive"))
    )
    (net (code "86") (name "ZED_D_SEL") (class "Default")
      (node (ref "J6") (pin "2") (pinfunction "2_2") (pintype "passive"))
      (node (ref "R3") (pin "P6") (pinfunction "2_P6") (pintype "passive"))
    )
    (net (code "87") (name "ZED_EXTINT") (class "Default")
      (node (ref "R9") (pin "P7") (pinfunction "2_P7") (pintype "passive"))
      (node (ref "U1") (pin "5") (pinfunction "Y1_5") (pintype "bidirectional"))
    )
    (net (code "88") (name "ZED_FENCE_STAT") (class "Default")
      (node (ref "J1") (pin "2") (pinfunction "2_2") (pintype "passive"))
      (node (ref "R4") (pin "P5") (pinfunction "2_P5") (pintype "passive"))
    )
    (net (code "89") (name "ZED_PPS_STAT") (class "Default")
      (node (ref "J6") (pin "5") (pinfunction "5_5") (pintype "passive"))
      (node (ref "R9") (pin "P8") (pinfunction "2_P8") (pintype "passive"))
      (node (ref "U1") (pin "14") (pinfunction "X1_14") (pintype "bidirectional"))
    )
    (net (code "90") (name "ZED_RTK_STAT") (class "Default")
      (node (ref "J1") (pin "3") (pinfunction "3_3") (pintype "passive"))
      (node (ref "R4") (pin "P6") (pinfunction "2_P6") (pintype "passive"))
    )
    (net (code "91") (name "ZED_~{RESET}") (class "Default")
      (node (ref "J6") (pin "3") (pinfunction "3_3") (pintype "passive"))
      (node (ref "R3") (pin "P7") (pinfunction "2_P7") (pintype "passive"))
    )
    (net (code "92") (name "ZED_~{SAFE}") (class "Default")
      (node (ref "J6") (pin "4") (pinfunction "4_4") (pintype "passive"))
      (node (ref "R3") (pin "P8") (pinfunction "2_P8") (pintype "passive"))
    )
    (net (code "93") (name "unconnected-(J8-PAD1-PadNC1)") (class "Default")
      (node (ref "J8") (pin "NC1") (pinfunction "PAD1_NC1") (pintype "bidirectional"))
    )
    (net (code "94") (name "unconnected-(J8-PAD2-PadNC2)") (class "Default")
      (node (ref "J8") (pin "NC2") (pinfunction "PAD2_NC2") (pintype "bidirectional"))
    )
    (net (code "95") (name "unconnected-(J16-DAT1{slash}NC-PadDAT1)") (class "Default")
      (node (ref "J16") (pin "DAT1") (pinfunction "DAT1/NC_DAT1") (pintype "bidirectional"))
    )
    (net (code "96") (name "unconnected-(J16-DAT2{slash}NC-PadDAT2)") (class "Default")
      (node (ref "J16") (pin "DAT2") (pinfunction "DAT2/NC_DAT2") (pintype "bidirectional"))
    )
    (net (code "97") (name "unconnected-(J20-Pad5)") (class "Default")
      (node (ref "J20") (pin "5") (pinfunction "5_5") (pintype "bidirectional"))
    )
    (net (code "98") (name "unconnected-(J20-Pad6)") (class "Default")
      (node (ref "J20") (pin "6") (pinfunction "6_6") (pintype "bidirectional"))
    )
    (net (code "99") (name "unconnected-(U2-NC-Pad4)") (class "Default")
      (node (ref "U2") (pin "4") (pinfunction "NC_4") (pintype "no_connect"))
    )
    (net (code "100") (name "unconnected-(U3-ANT_DETECT-Pad4)") (class "Default")
      (node (ref "U3") (pin "4") (pinfunction "ANT_DETECT_4") (pintype "bidirectional"))
    )
    (net (code "101") (name "unconnected-(U3-ANT_OFF-Pad5)") (class "Default")
      (node (ref "U3") (pin "5") (pinfunction "ANT_OFF_5") (pintype "bidirectional"))
    )
    (net (code "102") (name "unconnected-(U3-~{ANT_SHORT}-Pad6)") (class "Default")
      (node (ref "U3") (pin "6") (pinfunction "~{ANT_SHORT}_6") (pintype "bidirectional"))
    )
    (net (code "103") (name "unconnected-(U4-NC-Pad4)") (class "Default")
      (node (ref "U4") (pin "4") (pinfunction "NC_4") (pintype "no_connect"))
    )
    (net (code "104") (name "unconnected-(U6-R232-Pad15)") (class "Default")
      (node (ref "U6") (pin "15") (pinfunction "R232_15") (pintype "bidirectional"))
    )
    (net (code "105") (name "unconnected-(U6-~{CTS}-Pad9)") (class "Default")
      (node (ref "U6") (pin "9") (pinfunction "~{CTS}_9") (pintype "bidirectional"))
    )
    (net (code "106") (name "unconnected-(U6-~{DCD}-Pad12)") (class "Default")
      (node (ref "U6") (pin "12") (pinfunction "~{DCD}_12") (pintype "bidirectional"))
    )
    (net (code "107") (name "unconnected-(U6-~{DSR}-Pad10)") (class "Default")
      (node (ref "U6") (pin "10") (pinfunction "~{DSR}_10") (pintype "bidirectional"))
    )
    (net (code "108") (name "unconnected-(U6-~{RI}-Pad11)") (class "Default")
      (node (ref "U6") (pin "11") (pinfunction "~{RI}_11") (pintype "bidirectional"))
    )
    (net (code "109") (name "unconnected-(U7-~{ALRT}-Pad5)") (class "Default")
      (node (ref "U7") (pin "5") (pinfunction "~{ALRT}_5") (pintype "bidirectional"))
    )
    (net (code "110") (name "unconnected-(U10-STAT2-Pad4)") (class "Default")
      (node (ref "U10") (pin "4") (pinfunction "STAT2_4") (pintype "bidirectional"))
    )
    (net (code "111") (name "unconnected-(U10-~{PG}-Pad7)") (class "Default")
      (node (ref "U10") (pin "7") (pinfunction "~{PG}_7") (pintype "bidirectional"))
    )
    (net (code "112") (name "unconnected-(U13-INT2-Pad11)") (class "Default")
      (node (ref "U13") (pin "11") (pinfunction "INT2_11") (pintype "bidirectional"))
    )
  )
)
